# SparkFun_LIS3DH-Breakout.net
KiCad netlist of a schematic drawn in EAGLE
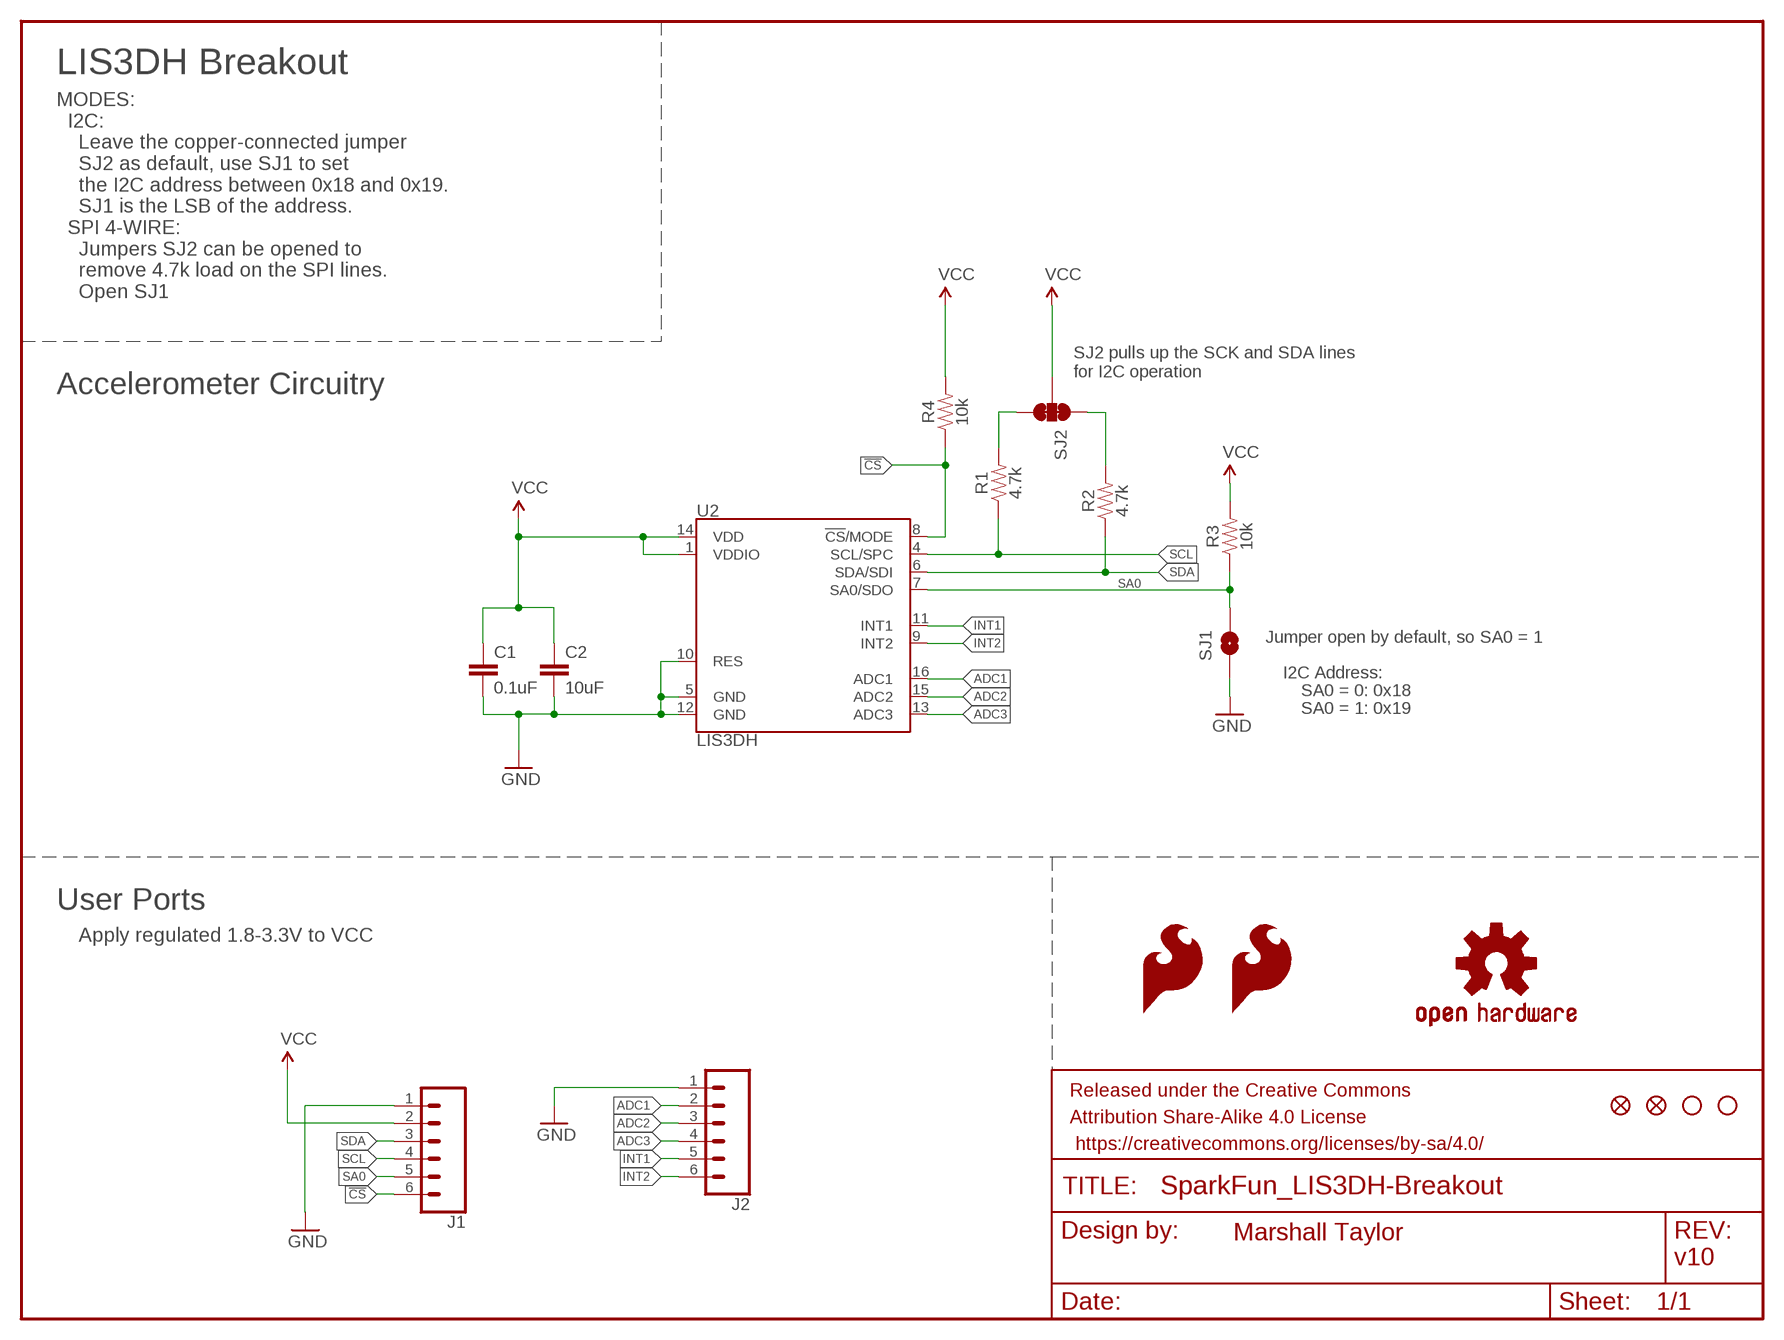
[diagram p0: schematic, sheet 1]

(export (version "E")
  (design (tool "Eeschema 10.0.6"))
  (components
    (comp (ref "C1")
      (value "0.1uF")
      (footprint "eagle-import:0402")
      (libsource (lib "eagle-import") (part "0.1UF-0402-16V-10%"))
    )
    (comp (ref "C2")
      (value "10uF")
      (footprint "eagle-import:0603")
      (libsource (lib "eagle-import") (part "10UF-0603-6.3V-20%"))
    )
    (comp (ref "FRAME2")
      (value "FRAME-LETTER")
      (footprint "eagle-import:CREATIVE_COMMONS")
      (libsource (lib "eagle-import") (part "FRAME-LETTER"))
    )
    (comp (ref "J1")
      (value "CONN_06NO_SILK_FEMALE_PTH")
      (footprint "eagle-import:1X06_NO_SILK")
      (libsource (lib "eagle-import") (part "CONN_06NO_SILK_FEMALE_PTH"))
    )
    (comp (ref "J2")
      (value "CONN_06NO_SILK_FEMALE_PTH")
      (footprint "eagle-import:1X06_NO_SILK")
      (libsource (lib "eagle-import") (part "CONN_06NO_SILK_FEMALE_PTH"))
    )
    (comp (ref "JP2")
      (value "FIDUCIALUFIDUCIAL")
      (footprint "eagle-import:MICRO-FIDUCIAL")
      (libsource (lib "eagle-import") (part "FIDUCIALUFIDUCIAL"))
    )
    (comp (ref "JP3")
      (value "STAND-OFF")
      (footprint "eagle-import:STAND-OFF")
      (libsource (lib "eagle-import") (part "STAND-OFF"))
    )
    (comp (ref "JP4")
      (value "STAND-OFF")
      (footprint "eagle-import:STAND-OFF")
      (libsource (lib "eagle-import") (part "STAND-OFF"))
    )
    (comp (ref "JP6")
      (value "FIDUCIALUFIDUCIAL")
      (footprint "eagle-import:MICRO-FIDUCIAL")
      (libsource (lib "eagle-import") (part "FIDUCIALUFIDUCIAL"))
    )
    (comp (ref "LOGO1")
      (value "SFE_LOGO_FLAME.1_INCH")
      (footprint "eagle-import:SFE_LOGO_FLAME_.1")
      (libsource (lib "eagle-import") (part "SFE_LOGO_FLAME.1_INCH"))
    )
    (comp (ref "LOGO2")
      (value "SFE_LOGO_FLAME.1_INCH")
      (footprint "eagle-import:SFE_LOGO_FLAME_.1")
      (libsource (lib "eagle-import") (part "SFE_LOGO_FLAME.1_INCH"))
    )
    (comp (ref "R1")
      (value "4.7k")
      (footprint "eagle-import:0603")
      (libsource (lib "eagle-import") (part "4.7KOHM-0603-1/10W-1%"))
    )
    (comp (ref "R2")
      (value "4.7k")
      (footprint "eagle-import:0603")
      (libsource (lib "eagle-import") (part "4.7KOHM-0603-1/10W-1%"))
    )
    (comp (ref "R3")
      (value "10k")
      (footprint "eagle-import:0603")
      (libsource (lib "eagle-import") (part "10KOHM-0603-1/10W-1%"))
    )
    (comp (ref "R4")
      (value "10k")
      (footprint "eagle-import:0603")
      (libsource (lib "eagle-import") (part "10KOHM-0603-1/10W-1%"))
    )
    (comp (ref "SJ1")
      (value "SOLDERJUMPERNO")
      (footprint "eagle-import:SJ_2S-NO")
      (libsource (lib "eagle-import") (part "SOLDERJUMPERNO"))
    )
    (comp (ref "SJ2")
      (value "JUMPER-PAD-3-NC_BY_TRACE")
      (footprint "eagle-import:PAD-JUMPER-3-3OF3_NC_BY_TRACE_YES_SILK_FULL_BOX")
      (libsource (lib "eagle-import") (part "JUMPER-PAD-3-NC_BY_TRACE"))
    )
    (comp (ref "U$1")
      (value "OSHW-LOGOS")
      (footprint "eagle-import:OSHW-LOGO-S")
      (libsource (lib "eagle-import") (part "OSHW-LOGOS"))
    )
    (comp (ref "U2")
      (value "LIS3DH")
      (footprint "eagle-import:LGA-16-3X3")
      (libsource (lib "eagle-import") (part "LIS3DH"))
    )
  )
  (nets
    (net (code "1") (name "/~{CS}") (class "Default")
      (node (ref "J1") (pin "6") (pinfunction "6_6") (pintype "passive"))
      (node (ref "R4") (pin "1") (pinfunction "1_1") (pintype "passive"))
      (node (ref "U2") (pin "8") (pinfunction "~{CS}/MODE_8") (pintype "bidirectional"))
    )
    (net (code "2") (name "ADC1") (class "Default")
      (node (ref "J2") (pin "2") (pinfunction "2_2") (pintype "passive"))
      (node (ref "U2") (pin "16") (pinfunction "ADC1_16") (pintype "bidirectional"))
    )
    (net (code "3") (name "ADC2") (class "Default")
      (node (ref "J2") (pin "3") (pinfunction "3_3") (pintype "passive"))
      (node (ref "U2") (pin "15") (pinfunction "ADC2_15") (pintype "bidirectional"))
    )
    (net (code "4") (name "ADC3") (class "Default")
      (node (ref "J2") (pin "4") (pinfunction "4_4") (pintype "passive"))
      (node (ref "U2") (pin "13") (pinfunction "ADC3_13") (pintype "bidirectional"))
    )
    (net (code "5") (name "GND") (class "Default")
      (node (ref "C1") (pin "2") (pinfunction "2_2") (pintype "passive"))
      (node (ref "C2") (pin "2") (pinfunction "2_2") (pintype "passive"))
      (node (ref "J1") (pin "1") (pinfunction "1_1") (pintype "passive"))
      (node (ref "J2") (pin "1") (pinfunction "1_1") (pintype "passive"))
      (node (ref "SJ1") (pin "1") (pinfunction "1_1") (pintype "passive"))
      (node (ref "U2") (pin "10") (pinfunction "RES_10") (pintype "bidirectional"))
      (node (ref "U2") (pin "12") (pinfunction "GND_12") (pintype "bidirectional"))
      (node (ref "U2") (pin "5") (pinfunction "GND_5") (pintype "bidirectional"))
    )
    (net (code "6") (name "INT1") (class "Default")
      (node (ref "J2") (pin "5") (pinfunction "5_5") (pintype "passive"))
      (node (ref "U2") (pin "11") (pinfunction "INT1_11") (pintype "bidirectional"))
    )
    (net (code "7") (name "INT2") (class "Default")
      (node (ref "J2") (pin "6") (pinfunction "6_6") (pintype "passive"))
      (node (ref "U2") (pin "9") (pinfunction "INT2_9") (pintype "bidirectional"))
    )
    (net (code "8") (name "Net-(R1-Pad2)") (class "Default")
      (node (ref "R1") (pin "2") (pinfunction "2_2") (pintype "passive"))
      (node (ref "SJ2") (pin "3") (pinfunction "3_3") (pintype "passive"))
    )
    (net (code "9") (name "Net-(R2-Pad2)") (class "Default")
      (node (ref "R2") (pin "2") (pinfunction "2_2") (pintype "passive"))
      (node (ref "SJ2") (pin "1") (pinfunction "1_1") (pintype "passive"))
    )
    (net (code "10") (name "SA0") (class "Default")
      (node (ref "J1") (pin "5") (pinfunction "5_5") (pintype "passive"))
      (node (ref "R3") (pin "1") (pinfunction "1_1") (pintype "passive"))
      (node (ref "SJ1") (pin "2") (pinfunction "2_2") (pintype "passive"))
      (node (ref "U2") (pin "7") (pinfunction "SA0/SDO_7") (pintype "bidirectional"))
    )
    (net (code "11") (name "SCL") (class "Default")
      (node (ref "J1") (pin "4") (pinfunction "4_4") (pintype "passive"))
      (node (ref "R1") (pin "1") (pinfunction "1_1") (pintype "passive"))
      (node (ref "U2") (pin "4") (pinfunction "SCL/SPC_4") (pintype "bidirectional"))
    )
    (net (code "12") (name "SDA") (class "Default")
      (node (ref "J1") (pin "3") (pinfunction "3_3") (pintype "passive"))
      (node (ref "R2") (pin "1") (pinfunction "1_1") (pintype "passive"))
      (node (ref "U2") (pin "6") (pinfunction "SDA/SDI_6") (pintype "bidirectional"))
    )
    (net (code "13") (name "VCC") (class "Default")
      (node (ref "C1") (pin "1") (pinfunction "1_1") (pintype "passive"))
      (node (ref "C2") (pin "1") (pinfunction "1_1") (pintype "passive"))
      (node (ref "J1") (pin "2") (pinfunction "2_2") (pintype "passive"))
      (node (ref "R3") (pin "2") (pinfunction "2_2") (pintype "passive"))
      (node (ref "R4") (pin "2") (pinfunction "2_2") (pintype "passive"))
      (node (ref "SJ2") (pin "2") (pinfunction "2_2") (pintype "passive"))
      (node (ref "U2") (pin "1") (pinfunction "VDDIO_1") (pintype "bidirectional"))
      (node (ref "U2") (pin "14") (pinfunction "VDD_14") (pintype "bidirectional"))
    )
  )
)
